# SCH.net
KiCad netlist of a schematic drawn in Altium Designer
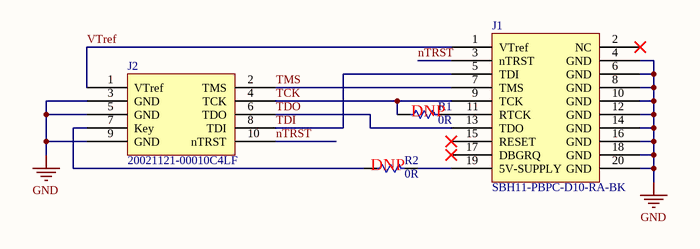
[diagram p0: SCH.SchDoc]

(export (version "E")
  (design (tool "Eeschema 10.0.6"))
  (components
    (comp (ref "J1")
      (value "SBH11-PBPC-D10-RA-BK")
      (footprint "20PIN_2.54")
      (description "CONN HEADR 2.54MM 20POS GOLD R/A")
      (fields (field (name "MANUFACTURER") "Sullins"))
      (libsource (lib "JTAG_SYMBOLS") (part "SBH11-PBPC-D10-RA-BK"))
    )
    (comp (ref "J2")
      (value "20021121-00010C4LF")
      (footprint "10PIN_1.27")
      (description "10 Positions Header, Unshrouded Connector 0.050\" (1.27mm) Surface Mount Gold")
      (fields (field (name "MANUFACTURER") "Amphenol FCI"))
      (libsource (lib "JTAG_SYMBOLS") (part "20021121-00010C4LF"))
    )
    (comp (ref "R1")
      (value "0R")
      (footprint "R0402")
      (description "RES SMD 0 OHM 1/16W 0402")
      (fields
        (field (name "MANUFACTURER") "Yageo")
        (field (name "MANUFACTURER PART NUMBER") "RC0402JR-070RL")
      )
      (libsource (lib "JTAG_SYMBOLS") (part "RC0402JR-070RL"))
    )
    (comp (ref "R2")
      (value "0R")
      (footprint "R0402")
      (description "RES SMD 0 OHM 1/16W 0402")
      (fields
        (field (name "MANUFACTURER") "Yageo")
        (field (name "MANUFACTURER PART NUMBER") "RC0402JR-070RL")
      )
      (libsource (lib "JTAG_SYMBOLS") (part "RC0402JR-070RL"))
    )
  )
  (nets
    (net (code "1") (name "/TCK") (class "Default")
      (node (ref "J1") (pin "9") (pinfunction "TCK_9") (pintype "passive"))
      (node (ref "J2") (pin "4") (pinfunction "TCK_4") (pintype "passive"))
      (node (ref "R1") (pin "1") (pinfunction "1_1") (pintype "passive"))
    )
    (net (code "2") (name "/TDI") (class "Default")
      (node (ref "J1") (pin "5") (pinfunction "TDI_5") (pintype "passive"))
      (node (ref "J2") (pin "8") (pinfunction "TDI_8") (pintype "passive"))
    )
    (net (code "3") (name "/TDO") (class "Default")
      (node (ref "J1") (pin "13") (pinfunction "TDO_13") (pintype "passive"))
      (node (ref "J2") (pin "6") (pinfunction "TDO_6") (pintype "passive"))
    )
    (net (code "4") (name "/TMS") (class "Default")
      (node (ref "J1") (pin "7") (pinfunction "TMS_7") (pintype "passive"))
      (node (ref "J2") (pin "2") (pinfunction "TMS_2") (pintype "passive"))
    )
    (net (code "5") (name "/VTref") (class "Default")
      (node (ref "J1") (pin "1") (pinfunction "VTref_1") (pintype "passive"))
      (node (ref "J2") (pin "1") (pinfunction "VTref_1") (pintype "passive"))
    )
    (net (code "6") (name "/nTRST") (class "Default")
      (node (ref "J1") (pin "3") (pinfunction "nTRST_3") (pintype "passive"))
      (node (ref "J2") (pin "10") (pinfunction "nTRST_10") (pintype "passive"))
    )
    (net (code "7") (name "GND") (class "Default")
      (node (ref "J1") (pin "10") (pinfunction "GND_10") (pintype "passive"))
      (node (ref "J1") (pin "12") (pinfunction "GND_12") (pintype "passive"))
      (node (ref "J1") (pin "14") (pinfunction "GND_14") (pintype "passive"))
      (node (ref "J1") (pin "16") (pinfunction "GND_16") (pintype "passive"))
      (node (ref "J1") (pin "18") (pinfunction "GND_18") (pintype "passive"))
      (node (ref "J1") (pin "20") (pinfunction "GND_20") (pintype "passive"))
      (node (ref "J1") (pin "4") (pinfunction "GND_4") (pintype "passive"))
      (node (ref "J1") (pin "6") (pinfunction "GND_6") (pintype "passive"))
      (node (ref "J1") (pin "8") (pinfunction "GND_8") (pintype "passive"))
      (node (ref "J2") (pin "3") (pinfunction "GND_3") (pintype "passive"))
      (node (ref "J2") (pin "5") (pinfunction "GND_5") (pintype "passive"))
      (node (ref "J2") (pin "9") (pinfunction "GND_9") (pintype "passive"))
    )
    (net (code "8") (name "Net-(J1-5V-SUPPLY)") (class "Default")
      (node (ref "J1") (pin "19") (pinfunction "5V-SUPPLY_19") (pintype "passive"))
      (node (ref "R2") (pin "2") (pinfunction "2_2") (pintype "passive"))
    )
    (net (code "9") (name "Net-(J1-RTCK)") (class "Default")
      (node (ref "J1") (pin "11") (pinfunction "RTCK_11") (pintype "passive"))
      (node (ref "R1") (pin "2") (pinfunction "2_2") (pintype "passive"))
    )
    (net (code "10") (name "Net-(J2-Key)") (class "Default")
      (node (ref "J2") (pin "7") (pinfunction "Key_7") (pintype "passive"))
      (node (ref "R2") (pin "1") (pinfunction "1_1") (pintype "passive"))
    )
    (net (code "11") (name "unconnected-(J1-DBGRQ-Pad17)") (class "Default")
      (node (ref "J1") (pin "17") (pinfunction "DBGRQ_17") (pintype "passive+no_connect"))
    )
    (net (code "12") (name "unconnected-(J1-NC-Pad2)") (class "Default")
      (node (ref "J1") (pin "2") (pinfunction "NC_2") (pintype "passive+no_connect"))
    )
    (net (code "13") (name "unconnected-(J1-RESET-Pad15)") (class "Default")
      (node (ref "J1") (pin "15") (pinfunction "RESET_15") (pintype "passive+no_connect"))
    )
  )
)
